# rf_bpf.net
KiCad netlist of a schematic drawn in Altium Designer
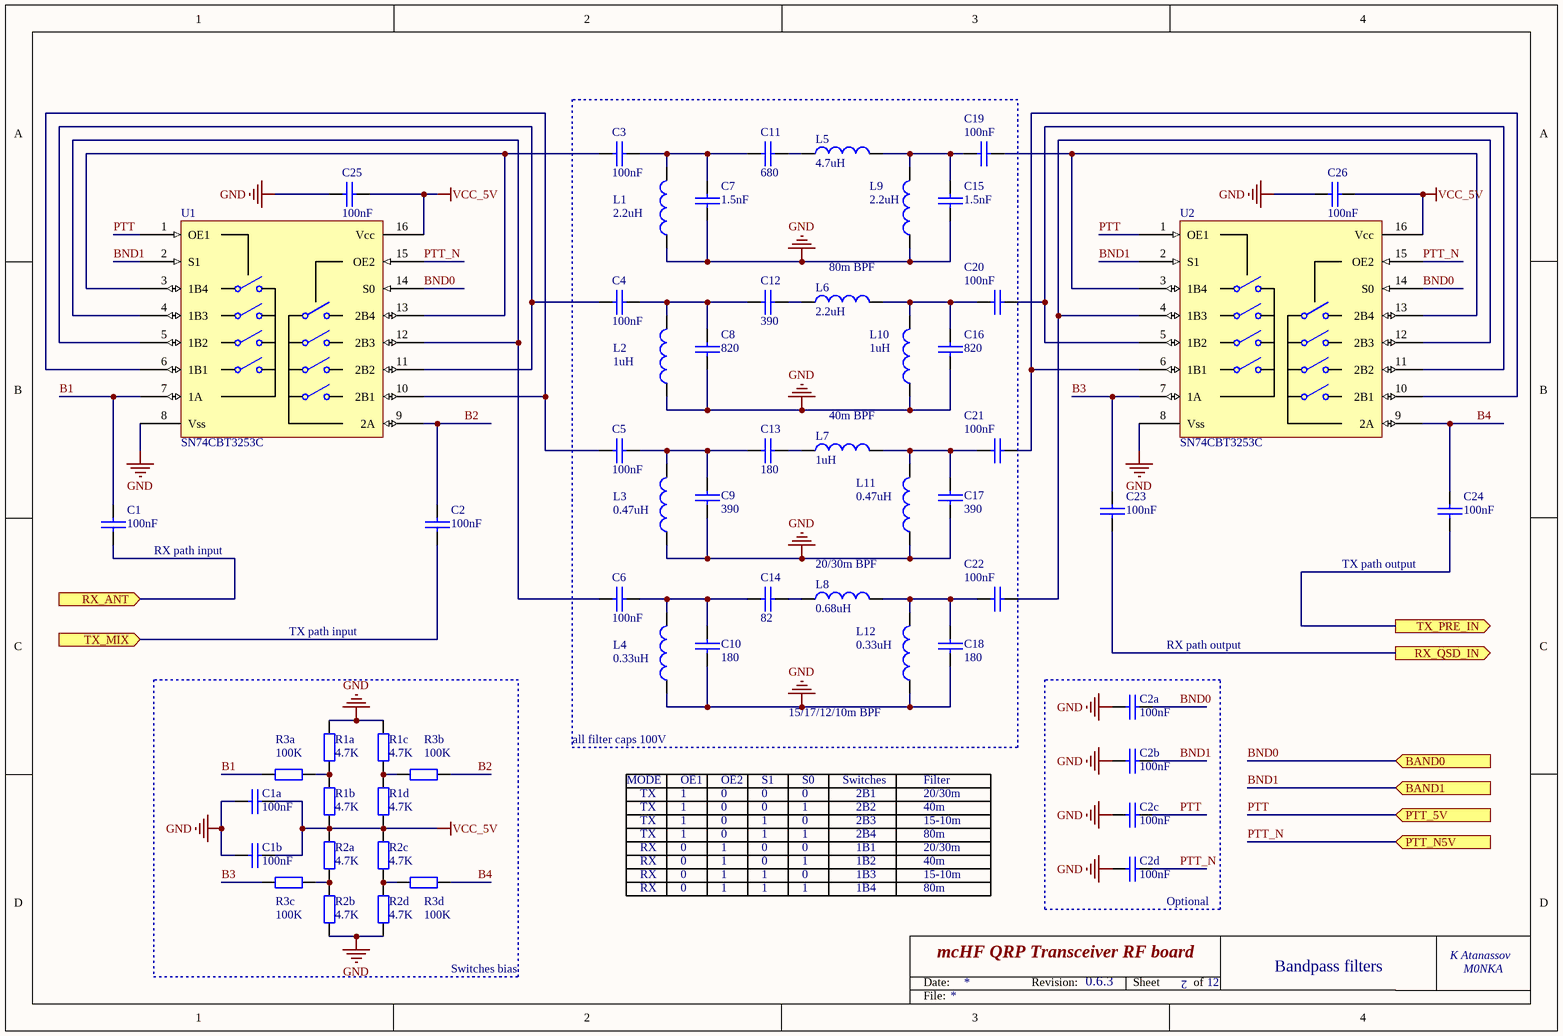
[diagram p0: rf_bpf.SchDoc]

(export (version "E")
  (design (tool "Eeschema 10.0.6"))
  (components
    (comp (ref "C1")
      (value "100nF")
      (footprint "0805-Pro")
      (description "Capacitor")
      (libsource (lib "mcHF_rf") (part "CAP"))
    )
    (comp (ref "C1a")
      (value "100nF")
      (footprint "0805-Pro")
      (description "Capacitor")
      (libsource (lib "mcHF_rf") (part "CAP"))
    )
    (comp (ref "C1b")
      (value "100nF")
      (footprint "0805-Pro")
      (description "Capacitor")
      (libsource (lib "mcHF_rf") (part "CAP"))
    )
    (comp (ref "C2")
      (value "100nF")
      (footprint "0805-Pro")
      (description "Capacitor")
      (libsource (lib "mcHF_rf") (part "CAP"))
    )
    (comp (ref "C2a")
      (value "100nF")
      (footprint "0805-Pro")
      (description "Capacitor")
      (libsource (lib "mcHF_rf") (part "CAP"))
    )
    (comp (ref "C2b")
      (value "100nF")
      (footprint "0805-Pro")
      (description "Capacitor")
      (libsource (lib "mcHF_rf") (part "CAP"))
    )
    (comp (ref "C2c")
      (value "100nF")
      (footprint "0805-Pro")
      (description "Capacitor")
      (libsource (lib "mcHF_rf") (part "CAP"))
    )
    (comp (ref "C2d")
      (value "100nF")
      (footprint "0805-Pro")
      (description "Capacitor")
      (libsource (lib "mcHF_rf") (part "CAP"))
    )
    (comp (ref "C3")
      (value "100nF")
      (footprint "0805-Pro")
      (description "Capacitor")
      (libsource (lib "mcHF_rf") (part "CAP"))
    )
    (comp (ref "C4")
      (value "100nF")
      (footprint "0805-Pro")
      (description "Capacitor")
      (libsource (lib "mcHF_rf") (part "CAP"))
    )
    (comp (ref "C5")
      (value "100nF")
      (footprint "0805-Pro")
      (description "Capacitor")
      (libsource (lib "mcHF_rf") (part "CAP"))
    )
    (comp (ref "C6")
      (value "100nF")
      (footprint "0805-Pro")
      (description "Capacitor")
      (libsource (lib "mcHF_rf") (part "CAP"))
    )
    (comp (ref "C7")
      (value "1.5nF")
      (footprint "0805-Pro")
      (description "Capacitor")
      (libsource (lib "mcHF_rf") (part "CAP"))
    )
    (comp (ref "C8")
      (value "820")
      (footprint "0805-Pro")
      (description "Capacitor")
      (libsource (lib "mcHF_rf") (part "CAP"))
    )
    (comp (ref "C9")
      (value "390")
      (footprint "0805-Pro")
      (description "Capacitor")
      (libsource (lib "mcHF_rf") (part "CAP"))
    )
    (comp (ref "C10")
      (value "180")
      (footprint "0805-Pro")
      (description "Capacitor")
      (libsource (lib "mcHF_rf") (part "CAP"))
    )
    (comp (ref "C11")
      (value "680")
      (footprint "0805-Pro")
      (description "Capacitor")
      (libsource (lib "mcHF_rf") (part "CAP"))
    )
    (comp (ref "C12")
      (value "390")
      (footprint "0805-Pro")
      (description "Capacitor")
      (libsource (lib "mcHF_rf") (part "CAP"))
    )
    (comp (ref "C13")
      (value "180")
      (footprint "0805-Pro")
      (description "Capacitor")
      (libsource (lib "mcHF_rf") (part "CAP"))
    )
    (comp (ref "C14")
      (value "82")
      (footprint "0805-Pro")
      (description "Capacitor")
      (libsource (lib "mcHF_rf") (part "CAP"))
    )
    (comp (ref "C15")
      (value "1.5nF")
      (footprint "0805-Pro")
      (description "Capacitor")
      (libsource (lib "mcHF_rf") (part "CAP"))
    )
    (comp (ref "C16")
      (value "820")
      (footprint "0805-Pro")
      (description "Capacitor")
      (libsource (lib "mcHF_rf") (part "CAP"))
    )
    (comp (ref "C17")
      (value "390")
      (footprint "0805-Pro")
      (description "Capacitor")
      (libsource (lib "mcHF_rf") (part "CAP"))
    )
    (comp (ref "C18")
      (value "180")
      (footprint "0805-Pro")
      (description "Capacitor")
      (libsource (lib "mcHF_rf") (part "CAP"))
    )
    (comp (ref "C19")
      (value "100nF")
      (footprint "0805-Pro")
      (description "Capacitor")
      (libsource (lib "mcHF_rf") (part "CAP"))
    )
    (comp (ref "C20")
      (value "100nF")
      (footprint "0805-Pro")
      (description "Capacitor")
      (libsource (lib "mcHF_rf") (part "CAP"))
    )
    (comp (ref "C21")
      (value "100nF")
      (footprint "0805-Pro")
      (description "Capacitor")
      (libsource (lib "mcHF_rf") (part "CAP"))
    )
    (comp (ref "C22")
      (value "100nF")
      (footprint "0805-Pro")
      (description "Capacitor")
      (libsource (lib "mcHF_rf") (part "CAP"))
    )
    (comp (ref "C23")
      (value "100nF")
      (footprint "0805-Pro")
      (description "Capacitor")
      (libsource (lib "mcHF_rf") (part "CAP"))
    )
    (comp (ref "C24")
      (value "100nF")
      (footprint "0805-Pro")
      (description "Capacitor")
      (libsource (lib "mcHF_rf") (part "CAP"))
    )
    (comp (ref "C25")
      (value "100nF")
      (footprint "0805-Pro")
      (description "Capacitor")
      (libsource (lib "mcHF_rf") (part "CAP"))
    )
    (comp (ref "C26")
      (value "100nF")
      (footprint "0805-Pro")
      (description "Capacitor")
      (libsource (lib "mcHF_rf") (part "CAP"))
    )
    (comp (ref "L1")
      (value "2.2uH")
      (footprint "0805-Pro")
      (description "INDUCTOR SMD")
      (libsource (lib "mcHF_rf") (part "BPF_IND"))
    )
    (comp (ref "L2")
      (value "1uH")
      (footprint "0805-Pro")
      (description "INDUCTOR SMD")
      (libsource (lib "mcHF_rf") (part "BPF_IND"))
    )
    (comp (ref "L3")
      (value "0.47uH")
      (footprint "0805-Pro")
      (description "INDUCTOR SMD")
      (libsource (lib "mcHF_rf") (part "BPF_IND"))
    )
    (comp (ref "L4")
      (value "0.33uH")
      (footprint "0805-Pro")
      (description "INDUCTOR SMD")
      (libsource (lib "mcHF_rf") (part "BPF_IND"))
    )
    (comp (ref "L5")
      (value "4.7uH")
      (footprint "0805-Pro")
      (description "INDUCTOR SMD")
      (libsource (lib "mcHF_rf") (part "BPF_IND"))
    )
    (comp (ref "L6")
      (value "2.2uH")
      (footprint "0805-Pro")
      (description "INDUCTOR SMD")
      (libsource (lib "mcHF_rf") (part "BPF_IND"))
    )
    (comp (ref "L7")
      (value "1uH")
      (footprint "0805-Pro")
      (description "INDUCTOR SMD")
      (libsource (lib "mcHF_rf") (part "BPF_IND"))
    )
    (comp (ref "L8")
      (value "0.68uH")
      (footprint "0805-Pro")
      (description "INDUCTOR SMD")
      (libsource (lib "mcHF_rf") (part "BPF_IND"))
    )
    (comp (ref "L9")
      (value "2.2uH")
      (footprint "0805-Pro")
      (description "INDUCTOR SMD")
      (libsource (lib "mcHF_rf") (part "BPF_IND"))
    )
    (comp (ref "L10")
      (value "1uH")
      (footprint "0805-Pro")
      (description "INDUCTOR SMD")
      (libsource (lib "mcHF_rf") (part "BPF_IND"))
    )
    (comp (ref "L11")
      (value "0.47uH")
      (footprint "0805-Pro")
      (description "INDUCTOR SMD")
      (libsource (lib "mcHF_rf") (part "BPF_IND"))
    )
    (comp (ref "L12")
      (value "0.33uH")
      (footprint "0805-Pro")
      (description "INDUCTOR SMD")
      (libsource (lib "mcHF_rf") (part "BPF_IND"))
    )
    (comp (ref "R1a")
      (value "4.7K")
      (footprint "0805-Pro")
      (description "Resistor")
      (libsource (lib "") (part "RES_1"))
    )
    (comp (ref "R1b")
      (value "4.7K")
      (footprint "0805-Pro")
      (description "Resistor")
      (libsource (lib "") (part "RES_1"))
    )
    (comp (ref "R1c")
      (value "4.7K")
      (footprint "0805-Pro")
      (description "Resistor")
      (libsource (lib "") (part "RES_1"))
    )
    (comp (ref "R1d")
      (value "4.7K")
      (footprint "0805-Pro")
      (description "Resistor")
      (libsource (lib "") (part "RES_1"))
    )
    (comp (ref "R2a")
      (value "4.7K")
      (footprint "0805-Pro")
      (description "Resistor")
      (libsource (lib "") (part "RES_1"))
    )
    (comp (ref "R2b")
      (value "4.7K")
      (footprint "0805-Pro")
      (description "Resistor")
      (libsource (lib "") (part "RES_1"))
    )
    (comp (ref "R2c")
      (value "4.7K")
      (footprint "0805-Pro")
      (description "Resistor")
      (libsource (lib "") (part "RES_1"))
    )
    (comp (ref "R2d")
      (value "4.7K")
      (footprint "0805-Pro")
      (description "Resistor")
      (libsource (lib "") (part "RES_1"))
    )
    (comp (ref "R3a")
      (value "100K")
      (footprint "0805-Pro")
      (description "Resistor")
      (libsource (lib "mcHF_rf") (part "RES"))
    )
    (comp (ref "R3b")
      (value "100K")
      (footprint "0805-Pro")
      (description "Resistor")
      (libsource (lib "mcHF_rf") (part "RES"))
    )
    (comp (ref "R3c")
      (value "100K")
      (footprint "0805-Pro")
      (description "Resistor")
      (libsource (lib "mcHF_rf") (part "RES"))
    )
    (comp (ref "R3d")
      (value "100K")
      (footprint "0805-Pro")
      (description "Resistor")
      (libsource (lib "mcHF_rf") (part "RES"))
    )
    (comp (ref "U1")
      (value "SN74CBT3253C")
      (footprint "SO-16-Pro")
      (description "Dual 4:1 Demux/Analog Switch")
      (libsource (lib "mcHF_rf") (part "SN74CBT3253C"))
    )
    (comp (ref "U2")
      (value "SN74CBT3253C")
      (footprint "SO-16-Pro")
      (description "Dual 4:1 Demux/Analog Switch")
      (libsource (lib "mcHF_rf") (part "SN74CBT3253C"))
    )
  )
  (nets
    (net (code "1") (name "/B1") (class "Default")
      (node (ref "C1") (pin "2") (pinfunction "2_2") (pintype "passive"))
      (node (ref "R3a") (pin "1") (pinfunction "1_1") (pintype "passive"))
      (node (ref "U1") (pin "7") (pinfunction "1A_7") (pintype "bidirectional"))
    )
    (net (code "2") (name "/B2") (class "Default")
      (node (ref "C2") (pin "2") (pinfunction "2_2") (pintype "passive"))
      (node (ref "R3b") (pin "2") (pinfunction "2_2") (pintype "passive"))
      (node (ref "U1") (pin "9") (pinfunction "2A_9") (pintype "bidirectional"))
    )
    (net (code "3") (name "/B3") (class "Default")
      (node (ref "C23") (pin "2") (pinfunction "2_2") (pintype "passive"))
      (node (ref "R3c") (pin "1") (pinfunction "1_1") (pintype "passive"))
      (node (ref "U2") (pin "7") (pinfunction "1A_7") (pintype "bidirectional"))
    )
    (net (code "4") (name "/B4") (class "Default")
      (node (ref "C24") (pin "2") (pinfunction "2_2") (pintype "passive"))
      (node (ref "R3d") (pin "2") (pinfunction "2_2") (pintype "passive"))
      (node (ref "U2") (pin "9") (pinfunction "2A_9") (pintype "bidirectional"))
    )
    (net (code "5") (name "/BND0") (class "Default")
      (node (ref "C2a") (pin "1") (pinfunction "1_1") (pintype "passive"))
      (node (ref "U1") (pin "14") (pinfunction "S0_14") (pintype "input"))
      (node (ref "U2") (pin "14") (pinfunction "S0_14") (pintype "input"))
    )
    (net (code "6") (name "/BND1") (class "Default")
      (node (ref "C2b") (pin "1") (pinfunction "1_1") (pintype "passive"))
      (node (ref "U1") (pin "2") (pinfunction "S1_2") (pintype "input"))
      (node (ref "U2") (pin "2") (pinfunction "S1_2") (pintype "input"))
    )
    (net (code "7") (name "/PTT") (class "Default")
      (node (ref "C2c") (pin "1") (pinfunction "1_1") (pintype "passive"))
      (node (ref "U1") (pin "1") (pinfunction "OE1_1") (pintype "input"))
      (node (ref "U2") (pin "1") (pinfunction "OE1_1") (pintype "input"))
    )
    (net (code "8") (name "/PTT_N") (class "Default")
      (node (ref "C2d") (pin "1") (pinfunction "1_1") (pintype "passive"))
      (node (ref "U1") (pin "15") (pinfunction "OE2_15") (pintype "input"))
      (node (ref "U2") (pin "15") (pinfunction "OE2_15") (pintype "input"))
    )
    (net (code "9") (name "/RX_ANT") (class "Default")
      (node (ref "C1") (pin "1") (pinfunction "1_1") (pintype "passive"))
    )
    (net (code "10") (name "/RX_QSD_IN") (class "Default")
      (node (ref "C23") (pin "1") (pinfunction "1_1") (pintype "passive"))
    )
    (net (code "11") (name "/TX_MIX") (class "Default")
      (node (ref "C2") (pin "1") (pinfunction "1_1") (pintype "passive"))
    )
    (net (code "12") (name "/TX_PRE_IN") (class "Default")
      (node (ref "C24") (pin "1") (pinfunction "1_1") (pintype "passive"))
    )
    (net (code "13") (name "GND") (class "Default")
      (node (ref "C10") (pin "1") (pinfunction "1_1") (pintype "passive"))
      (node (ref "C15") (pin "2") (pinfunction "2_2") (pintype "passive"))
      (node (ref "C16") (pin "2") (pinfunction "2_2") (pintype "passive"))
      (node (ref "C17") (pin "1") (pinfunction "1_1") (pintype "passive"))
      (node (ref "C18") (pin "1") (pinfunction "1_1") (pintype "passive"))
      (node (ref "C1a") (pin "2") (pinfunction "2_2") (pintype "passive"))
      (node (ref "C1b") (pin "2") (pinfunction "2_2") (pintype "passive"))
      (node (ref "C25") (pin "2") (pinfunction "2_2") (pintype "passive"))
      (node (ref "C26") (pin "2") (pinfunction "2_2") (pintype "passive"))
      (node (ref "C2a") (pin "2") (pinfunction "2_2") (pintype "passive"))
      (node (ref "C2b") (pin "2") (pinfunction "2_2") (pintype "passive"))
      (node (ref "C2c") (pin "2") (pinfunction "2_2") (pintype "passive"))
      (node (ref "C2d") (pin "2") (pinfunction "2_2") (pintype "passive"))
      (node (ref "C7") (pin "2") (pinfunction "2_2") (pintype "passive"))
      (node (ref "C8") (pin "2") (pinfunction "2_2") (pintype "passive"))
      (node (ref "C9") (pin "1") (pinfunction "1_1") (pintype "passive"))
      (node (ref "L1") (pin "1") (pinfunction "1_1") (pintype "passive"))
      (node (ref "L10") (pin "1") (pinfunction "1_1") (pintype "passive"))
      (node (ref "L11") (pin "1") (pinfunction "1_1") (pintype "passive"))
      (node (ref "L12") (pin "1") (pinfunction "1_1") (pintype "passive"))
      (node (ref "L2") (pin "1") (pinfunction "1_1") (pintype "passive"))
      (node (ref "L3") (pin "1") (pinfunction "1_1") (pintype "passive"))
      (node (ref "L4") (pin "1") (pinfunction "1_1") (pintype "passive"))
      (node (ref "L9") (pin "1") (pinfunction "1_1") (pintype "passive"))
      (node (ref "R1a") (pin "1") (pinfunction "1_1") (pintype "passive"))
      (node (ref "R1c") (pin "1") (pinfunction "1_1") (pintype "passive"))
      (node (ref "R2b") (pin "2") (pinfunction "2_2") (pintype "passive"))
      (node (ref "R2d") (pin "2") (pinfunction "2_2") (pintype "passive"))
      (node (ref "U1") (pin "8") (pinfunction "Vss_8") (pintype "power_in"))
      (node (ref "U2") (pin "8") (pinfunction "Vss_8") (pintype "power_in"))
    )
    (net (code "14") (name "Net-(C10-Pad2)") (class "Default")
      (node (ref "C10") (pin "2") (pinfunction "2_2") (pintype "passive"))
      (node (ref "C14") (pin "1") (pinfunction "1_1") (pintype "passive"))
      (node (ref "C6") (pin "1") (pinfunction "1_1") (pintype "passive"))
      (node (ref "L4") (pin "2") (pinfunction "2_2") (pintype "passive"))
    )
    (net (code "15") (name "Net-(C11-Pad1)") (class "Default")
      (node (ref "C11") (pin "1") (pinfunction "1_1") (pintype "passive"))
      (node (ref "C3") (pin "1") (pinfunction "1_1") (pintype "passive"))
      (node (ref "C7") (pin "1") (pinfunction "1_1") (pintype "passive"))
      (node (ref "L1") (pin "2") (pinfunction "2_2") (pintype "passive"))
    )
    (net (code "16") (name "Net-(C11-Pad2)") (class "Default")
      (node (ref "C11") (pin "2") (pinfunction "2_2") (pintype "passive"))
      (node (ref "L5") (pin "1") (pinfunction "1_1") (pintype "passive"))
    )
    (net (code "17") (name "Net-(C12-Pad1)") (class "Default")
      (node (ref "C12") (pin "1") (pinfunction "1_1") (pintype "passive"))
      (node (ref "C4") (pin "1") (pinfunction "1_1") (pintype "passive"))
      (node (ref "C8") (pin "1") (pinfunction "1_1") (pintype "passive"))
      (node (ref "L2") (pin "2") (pinfunction "2_2") (pintype "passive"))
    )
    (net (code "18") (name "Net-(C12-Pad2)") (class "Default")
      (node (ref "C12") (pin "2") (pinfunction "2_2") (pintype "passive"))
      (node (ref "L6") (pin "1") (pinfunction "1_1") (pintype "passive"))
    )
    (net (code "19") (name "Net-(C13-Pad1)") (class "Default")
      (node (ref "C13") (pin "1") (pinfunction "1_1") (pintype "passive"))
      (node (ref "C5") (pin "1") (pinfunction "1_1") (pintype "passive"))
      (node (ref "C9") (pin "2") (pinfunction "2_2") (pintype "passive"))
      (node (ref "L3") (pin "2") (pinfunction "2_2") (pintype "passive"))
    )
    (net (code "20") (name "Net-(C13-Pad2)") (class "Default")
      (node (ref "C13") (pin "2") (pinfunction "2_2") (pintype "passive"))
      (node (ref "L7") (pin "1") (pinfunction "1_1") (pintype "passive"))
    )
    (net (code "21") (name "Net-(C14-Pad2)") (class "Default")
      (node (ref "C14") (pin "2") (pinfunction "2_2") (pintype "passive"))
      (node (ref "L8") (pin "1") (pinfunction "1_1") (pintype "passive"))
    )
    (net (code "22") (name "Net-(C15-Pad1)") (class "Default")
      (node (ref "C15") (pin "1") (pinfunction "1_1") (pintype "passive"))
      (node (ref "C19") (pin "2") (pinfunction "2_2") (pintype "passive"))
      (node (ref "L5") (pin "2") (pinfunction "2_2") (pintype "passive"))
      (node (ref "L9") (pin "2") (pinfunction "2_2") (pintype "passive"))
    )
    (net (code "23") (name "Net-(C16-Pad1)") (class "Default")
      (node (ref "C16") (pin "1") (pinfunction "1_1") (pintype "passive"))
      (node (ref "C20") (pin "2") (pinfunction "2_2") (pintype "passive"))
      (node (ref "L10") (pin "2") (pinfunction "2_2") (pintype "passive"))
      (node (ref "L6") (pin "2") (pinfunction "2_2") (pintype "passive"))
    )
    (net (code "24") (name "Net-(C17-Pad2)") (class "Default")
      (node (ref "C17") (pin "2") (pinfunction "2_2") (pintype "passive"))
      (node (ref "C21") (pin "2") (pinfunction "2_2") (pintype "passive"))
      (node (ref "L11") (pin "2") (pinfunction "2_2") (pintype "passive"))
      (node (ref "L7") (pin "2") (pinfunction "2_2") (pintype "passive"))
    )
    (net (code "25") (name "Net-(C18-Pad2)") (class "Default")
      (node (ref "C18") (pin "2") (pinfunction "2_2") (pintype "passive"))
      (node (ref "C22") (pin "2") (pinfunction "2_2") (pintype "passive"))
      (node (ref "L12") (pin "2") (pinfunction "2_2") (pintype "passive"))
      (node (ref "L8") (pin "2") (pinfunction "2_2") (pintype "passive"))
    )
    (net (code "26") (name "Net-(R1a-Pad2)") (class "Default")
      (node (ref "R1a") (pin "2") (pinfunction "2_2") (pintype "passive"))
      (node (ref "R1b") (pin "1") (pinfunction "1_1") (pintype "passive"))
      (node (ref "R3a") (pin "2") (pinfunction "2_2") (pintype "passive"))
    )
    (net (code "27") (name "Net-(R1c-Pad2)") (class "Default")
      (node (ref "R1c") (pin "2") (pinfunction "2_2") (pintype "passive"))
      (node (ref "R1d") (pin "1") (pinfunction "1_1") (pintype "passive"))
      (node (ref "R3b") (pin "1") (pinfunction "1_1") (pintype "passive"))
    )
    (net (code "28") (name "Net-(R2a-Pad2)") (class "Default")
      (node (ref "R2a") (pin "2") (pinfunction "2_2") (pintype "passive"))
      (node (ref "R2b") (pin "1") (pinfunction "1_1") (pintype "passive"))
      (node (ref "R3c") (pin "2") (pinfunction "2_2") (pintype "passive"))
    )
    (net (code "29") (name "Net-(R2c-Pad2)") (class "Default")
      (node (ref "R2c") (pin "2") (pinfunction "2_2") (pintype "passive"))
      (node (ref "R2d") (pin "1") (pinfunction "1_1") (pintype "passive"))
      (node (ref "R3d") (pin "1") (pinfunction "1_1") (pintype "passive"))
    )
    (net (code "30") (name "Net-(U1-1B1)") (class "Default")
      (node (ref "C5") (pin "2") (pinfunction "2_2") (pintype "passive"))
      (node (ref "U1") (pin "10") (pinfunction "2B1_10") (pintype "bidirectional"))
      (node (ref "U1") (pin "6") (pinfunction "1B1_6") (pintype "bidirectional"))
    )
    (net (code "31") (name "Net-(U1-1B2)") (class "Default")
      (node (ref "C4") (pin "2") (pinfunction "2_2") (pintype "passive"))
      (node (ref "U1") (pin "11") (pinfunction "2B2_11") (pintype "bidirectional"))
      (node (ref "U1") (pin "5") (pinfunction "1B2_5") (pintype "bidirectional"))
    )
    (net (code "32") (name "Net-(U1-1B3)") (class "Default")
      (node (ref "C6") (pin "2") (pinfunction "2_2") (pintype "passive"))
      (node (ref "U1") (pin "12") (pinfunction "2B3_12") (pintype "bidirectional"))
      (node (ref "U1") (pin "4") (pinfunction "1B3_4") (pintype "bidirectional"))
    )
    (net (code "33") (name "Net-(U1-1B4)") (class "Default")
      (node (ref "C3") (pin "2") (pinfunction "2_2") (pintype "passive"))
      (node (ref "U1") (pin "13") (pinfunction "2B4_13") (pintype "bidirectional"))
      (node (ref "U1") (pin "3") (pinfunction "1B4_3") (pintype "bidirectional"))
    )
    (net (code "34") (name "Net-(U2-1B1)") (class "Default")
      (node (ref "C21") (pin "1") (pinfunction "1_1") (pintype "passive"))
      (node (ref "U2") (pin "10") (pinfunction "2B1_10") (pintype "bidirectional"))
      (node (ref "U2") (pin "6") (pinfunction "1B1_6") (pintype "bidirectional"))
    )
    (net (code "35") (name "Net-(U2-1B2)") (class "Default")
      (node (ref "C20") (pin "1") (pinfunction "1_1") (pintype "passive"))
      (node (ref "U2") (pin "11") (pinfunction "2B2_11") (pintype "bidirectional"))
      (node (ref "U2") (pin "5") (pinfunction "1B2_5") (pintype "bidirectional"))
    )
    (net (code "36") (name "Net-(U2-1B3)") (class "Default")
      (node (ref "C22") (pin "1") (pinfunction "1_1") (pintype "passive"))
      (node (ref "U2") (pin "12") (pinfunction "2B3_12") (pintype "bidirectional"))
      (node (ref "U2") (pin "4") (pinfunction "1B3_4") (pintype "bidirectional"))
    )
    (net (code "37") (name "Net-(U2-1B4)") (class "Default")
      (node (ref "C19") (pin "1") (pinfunction "1_1") (pintype "passive"))
      (node (ref "U2") (pin "13") (pinfunction "2B4_13") (pintype "bidirectional"))
      (node (ref "U2") (pin "3") (pinfunction "1B4_3") (pintype "bidirectional"))
    )
    (net (code "38") (name "VCC_5V") (class "Default")
      (node (ref "C1a") (pin "1") (pinfunction "1_1") (pintype "passive"))
      (node (ref "C1b") (pin "1") (pinfunction "1_1") (pintype "passive"))
      (node (ref "C25") (pin "1") (pinfunction "1_1") (pintype "passive"))
      (node (ref "C26") (pin "1") (pinfunction "1_1") (pintype "passive"))
      (node (ref "R1b") (pin "2") (pinfunction "2_2") (pintype "passive"))
      (node (ref "R1d") (pin "2") (pinfunction "2_2") (pintype "passive"))
      (node (ref "R2a") (pin "1") (pinfunction "1_1") (pintype "passive"))
      (node (ref "R2c") (pin "1") (pinfunction "1_1") (pintype "passive"))
      (node (ref "U1") (pin "16") (pinfunction "Vcc_16") (pintype "power_in"))
      (node (ref "U2") (pin "16") (pinfunction "Vcc_16") (pintype "power_in"))
    )
  )
)
